# Keypad_0_0.net
KiCad netlist of a schematic drawn in EAGLE
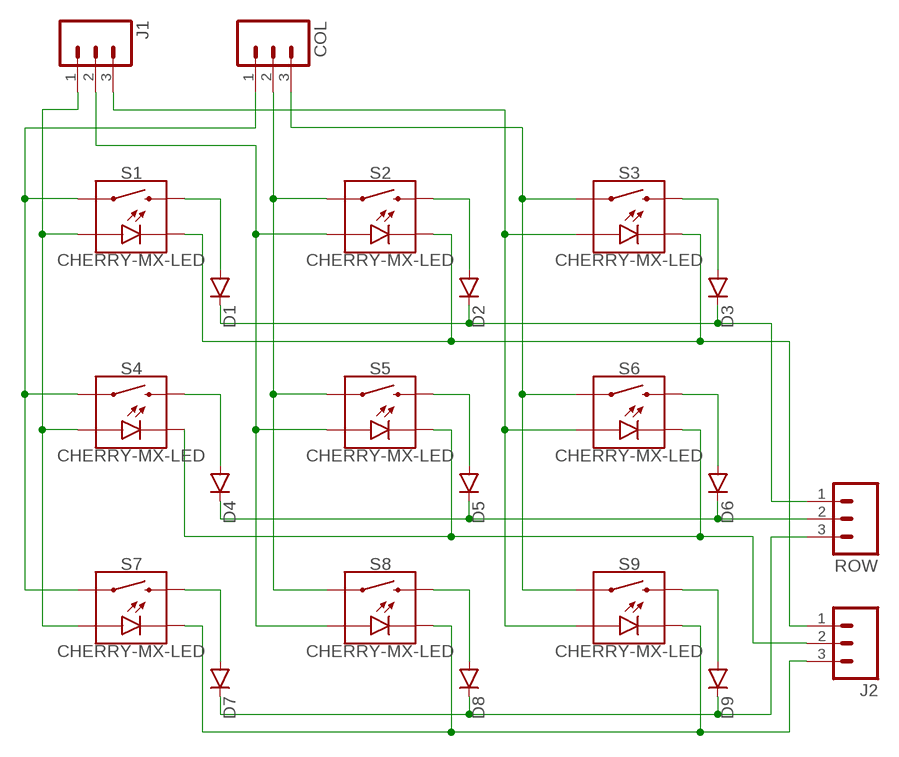
[diagram p0: schematic, sheet 1]

(export (version "E")
  (design (tool "Eeschema 10.0.6"))
  (components
    (comp (ref "COL")
      (value "M03LOCK")
      (footprint "eagle-import:1X03_LOCK")
      (libsource (lib "eagle-import") (part "M03LOCK"))
    )
    (comp (ref "D1")
      (value "DIODESOT23")
      (footprint "eagle-import:SOT23-3")
      (libsource (lib "eagle-import") (part "DIODESOT23"))
    )
    (comp (ref "D2")
      (value "DIODESOT23")
      (footprint "eagle-import:SOT23-3")
      (libsource (lib "eagle-import") (part "DIODESOT23"))
    )
    (comp (ref "D3")
      (value "DIODESOT23")
      (footprint "eagle-import:SOT23-3")
      (libsource (lib "eagle-import") (part "DIODESOT23"))
    )
    (comp (ref "D4")
      (value "DIODESOT23")
      (footprint "eagle-import:SOT23-3")
      (libsource (lib "eagle-import") (part "DIODESOT23"))
    )
    (comp (ref "D5")
      (value "DIODESOT23")
      (footprint "eagle-import:SOT23-3")
      (libsource (lib "eagle-import") (part "DIODESOT23"))
    )
    (comp (ref "D6")
      (value "DIODESOT23")
      (footprint "eagle-import:SOT23-3")
      (libsource (lib "eagle-import") (part "DIODESOT23"))
    )
    (comp (ref "D7")
      (value "DIODESOT23")
      (footprint "eagle-import:SOT23-3")
      (libsource (lib "eagle-import") (part "DIODESOT23"))
    )
    (comp (ref "D8")
      (value "DIODESOT23")
      (footprint "eagle-import:SOT23-3")
      (libsource (lib "eagle-import") (part "DIODESOT23"))
    )
    (comp (ref "D9")
      (value "DIODESOT23")
      (footprint "eagle-import:SOT23-3")
      (libsource (lib "eagle-import") (part "DIODESOT23"))
    )
    (comp (ref "J1")
      (value "M03LOCK")
      (footprint "eagle-import:1X03_LOCK")
      (libsource (lib "eagle-import") (part "M03LOCK"))
    )
    (comp (ref "J2")
      (value "M03LOCK")
      (footprint "eagle-import:1X03_LOCK")
      (libsource (lib "eagle-import") (part "M03LOCK"))
    )
    (comp (ref "ROW")
      (value "M03LOCK")
      (footprint "eagle-import:1X03_LOCK")
      (libsource (lib "eagle-import") (part "M03LOCK"))
    )
    (comp (ref "S1")
      (value "CHERRY-MX-LED")
      (footprint "eagle-import:CHERRY-MX-LED")
      (libsource (lib "eagle-import") (part "CHERRY-MX-LED"))
    )
    (comp (ref "S2")
      (value "CHERRY-MX-LED")
      (footprint "eagle-import:CHERRY-MX-LED")
      (libsource (lib "eagle-import") (part "CHERRY-MX-LED"))
    )
    (comp (ref "S3")
      (value "CHERRY-MX-LED")
      (footprint "eagle-import:CHERRY-MX-LED")
      (libsource (lib "eagle-import") (part "CHERRY-MX-LED"))
    )
    (comp (ref "S4")
      (value "CHERRY-MX-LED")
      (footprint "eagle-import:CHERRY-MX-LED")
      (libsource (lib "eagle-import") (part "CHERRY-MX-LED"))
    )
    (comp (ref "S5")
      (value "CHERRY-MX-LED")
      (footprint "eagle-import:CHERRY-MX-LED")
      (libsource (lib "eagle-import") (part "CHERRY-MX-LED"))
    )
    (comp (ref "S6")
      (value "CHERRY-MX-LED")
      (footprint "eagle-import:CHERRY-MX-LED")
      (libsource (lib "eagle-import") (part "CHERRY-MX-LED"))
    )
    (comp (ref "S7")
      (value "CHERRY-MX-LED")
      (footprint "eagle-import:CHERRY-MX-LED")
      (libsource (lib "eagle-import") (part "CHERRY-MX-LED"))
    )
    (comp (ref "S8")
      (value "CHERRY-MX-LED")
      (footprint "eagle-import:CHERRY-MX-LED")
      (libsource (lib "eagle-import") (part "CHERRY-MX-LED"))
    )
    (comp (ref "S9")
      (value "CHERRY-MX-LED")
      (footprint "eagle-import:CHERRY-MX-LED")
      (libsource (lib "eagle-import") (part "CHERRY-MX-LED"))
    )
  )
  (nets
    (net (code "1") (name "Net-(COL-Pad1)") (class "Default")
      (node (ref "COL") (pin "1") (pinfunction "1_1") (pintype "passive"))
      (node (ref "S1") (pin "S1") (pinfunction "S1_S1") (pintype "passive"))
      (node (ref "S4") (pin "S1") (pinfunction "S1_S1") (pintype "passive"))
      (node (ref "S7") (pin "S1") (pinfunction "S1_S1") (pintype "passive"))
    )
    (net (code "2") (name "Net-(COL-Pad2)") (class "Default")
      (node (ref "COL") (pin "2") (pinfunction "2_2") (pintype "passive"))
      (node (ref "S2") (pin "S1") (pinfunction "S1_S1") (pintype "passive"))
      (node (ref "S5") (pin "S1") (pinfunction "S1_S1") (pintype "passive"))
      (node (ref "S8") (pin "S1") (pinfunction "S1_S1") (pintype "passive"))
    )
    (net (code "3") (name "Net-(COL-Pad3)") (class "Default")
      (node (ref "COL") (pin "3") (pinfunction "3_3") (pintype "passive"))
      (node (ref "S3") (pin "S1") (pinfunction "S1_S1") (pintype "passive"))
      (node (ref "S6") (pin "S1") (pinfunction "S1_S1") (pintype "passive"))
      (node (ref "S9") (pin "S1") (pinfunction "S1_S1") (pintype "passive"))
    )
    (net (code "4") (name "Net-(D1-A)") (class "Default")
      (node (ref "D1") (pin "1") (pinfunction "A_1") (pintype "passive"))
      (node (ref "S1") (pin "S2") (pinfunction "S2_S2") (pintype "passive"))
    )
    (net (code "5") (name "Net-(D1-C)") (class "Default")
      (node (ref "D1") (pin "3") (pinfunction "C_3") (pintype "passive"))
      (node (ref "D2") (pin "3") (pinfunction "C_3") (pintype "passive"))
      (node (ref "D3") (pin "3") (pinfunction "C_3") (pintype "passive"))
      (node (ref "ROW") (pin "1") (pinfunction "1_1") (pintype "passive"))
    )
    (net (code "6") (name "Net-(D2-A)") (class "Default")
      (node (ref "D2") (pin "1") (pinfunction "A_1") (pintype "passive"))
      (node (ref "S2") (pin "S2") (pinfunction "S2_S2") (pintype "passive"))
    )
    (net (code "7") (name "Net-(D3-A)") (class "Default")
      (node (ref "D3") (pin "1") (pinfunction "A_1") (pintype "passive"))
      (node (ref "S3") (pin "S2") (pinfunction "S2_S2") (pintype "passive"))
    )
    (net (code "8") (name "Net-(D4-A)") (class "Default")
      (node (ref "D4") (pin "1") (pinfunction "A_1") (pintype "passive"))
      (node (ref "S4") (pin "S2") (pinfunction "S2_S2") (pintype "passive"))
    )
    (net (code "9") (name "Net-(D4-C)") (class "Default")
      (node (ref "D4") (pin "3") (pinfunction "C_3") (pintype "passive"))
      (node (ref "D5") (pin "3") (pinfunction "C_3") (pintype "passive"))
      (node (ref "D6") (pin "3") (pinfunction "C_3") (pintype "passive"))
      (node (ref "ROW") (pin "2") (pinfunction "2_2") (pintype "passive"))
    )
    (net (code "10") (name "Net-(D5-A)") (class "Default")
      (node (ref "D5") (pin "1") (pinfunction "A_1") (pintype "passive"))
      (node (ref "S5") (pin "S2") (pinfunction "S2_S2") (pintype "passive"))
    )
    (net (code "11") (name "Net-(D6-A)") (class "Default")
      (node (ref "D6") (pin "1") (pinfunction "A_1") (pintype "passive"))
      (node (ref "S6") (pin "S2") (pinfunction "S2_S2") (pintype "passive"))
    )
    (net (code "12") (name "Net-(D7-A)") (class "Default")
      (node (ref "D7") (pin "1") (pinfunction "A_1") (pintype "passive"))
      (node (ref "S7") (pin "S2") (pinfunction "S2_S2") (pintype "passive"))
    )
    (net (code "13") (name "Net-(D7-C)") (class "Default")
      (node (ref "D7") (pin "3") (pinfunction "C_3") (pintype "passive"))
      (node (ref "D8") (pin "3") (pinfunction "C_3") (pintype "passive"))
      (node (ref "D9") (pin "3") (pinfunction "C_3") (pintype "passive"))
      (node (ref "ROW") (pin "3") (pinfunction "3_3") (pintype "passive"))
    )
    (net (code "14") (name "Net-(D8-A)") (class "Default")
      (node (ref "D8") (pin "1") (pinfunction "A_1") (pintype "passive"))
      (node (ref "S8") (pin "S2") (pinfunction "S2_S2") (pintype "passive"))
    )
    (net (code "15") (name "Net-(D9-A)") (class "Default")
      (node (ref "D9") (pin "1") (pinfunction "A_1") (pintype "passive"))
      (node (ref "S9") (pin "S2") (pinfunction "S2_S2") (pintype "passive"))
    )
    (net (code "16") (name "Net-(J1-Pad1)") (class "Default")
      (node (ref "J1") (pin "1") (pinfunction "1_1") (pintype "passive"))
      (node (ref "S1") (pin "A") (pinfunction "A_A") (pintype "passive"))
      (node (ref "S4") (pin "A") (pinfunction "A_A") (pintype "passive"))
      (node (ref "S7") (pin "A") (pinfunction "A_A") (pintype "passive"))
    )
    (net (code "17") (name "Net-(J1-Pad2)") (class "Default")
      (node (ref "J1") (pin "2") (pinfunction "2_2") (pintype "passive"))
      (node (ref "S2") (pin "A") (pinfunction "A_A") (pintype "passive"))
      (node (ref "S5") (pin "A") (pinfunction "A_A") (pintype "passive"))
      (node (ref "S8") (pin "A") (pinfunction "A_A") (pintype "passive"))
    )
    (net (code "18") (name "Net-(J1-Pad3)") (class "Default")
      (node (ref "J1") (pin "3") (pinfunction "3_3") (pintype "passive"))
      (node (ref "S3") (pin "A") (pinfunction "A_A") (pintype "passive"))
      (node (ref "S6") (pin "A") (pinfunction "A_A") (pintype "passive"))
      (node (ref "S9") (pin "A") (pinfunction "A_A") (pintype "passive"))
    )
    (net (code "19") (name "Net-(S1-C)") (class "Default")
      (node (ref "J2") (pin "1") (pinfunction "1_1") (pintype "passive"))
      (node (ref "S1") (pin "K") (pinfunction "C_K") (pintype "passive"))
      (node (ref "S2") (pin "K") (pinfunction "C_K") (pintype "passive"))
      (node (ref "S3") (pin "K") (pinfunction "C_K") (pintype "passive"))
    )
    (net (code "20") (name "Net-(S4-C)") (class "Default")
      (node (ref "J2") (pin "2") (pinfunction "2_2") (pintype "passive"))
      (node (ref "S4") (pin "K") (pinfunction "C_K") (pintype "passive"))
      (node (ref "S5") (pin "K") (pinfunction "C_K") (pintype "passive"))
      (node (ref "S6") (pin "K") (pinfunction "C_K") (pintype "passive"))
    )
    (net (code "21") (name "Net-(S7-C)") (class "Default")
      (node (ref "J2") (pin "3") (pinfunction "3_3") (pintype "passive"))
      (node (ref "S7") (pin "K") (pinfunction "C_K") (pintype "passive"))
      (node (ref "S8") (pin "K") (pinfunction "C_K") (pintype "passive"))
      (node (ref "S9") (pin "K") (pinfunction "C_K") (pintype "passive"))
    )
  )
)
